# DMX8x8A-v1.net
KiCad netlist of a schematic drawn in Altium Designer
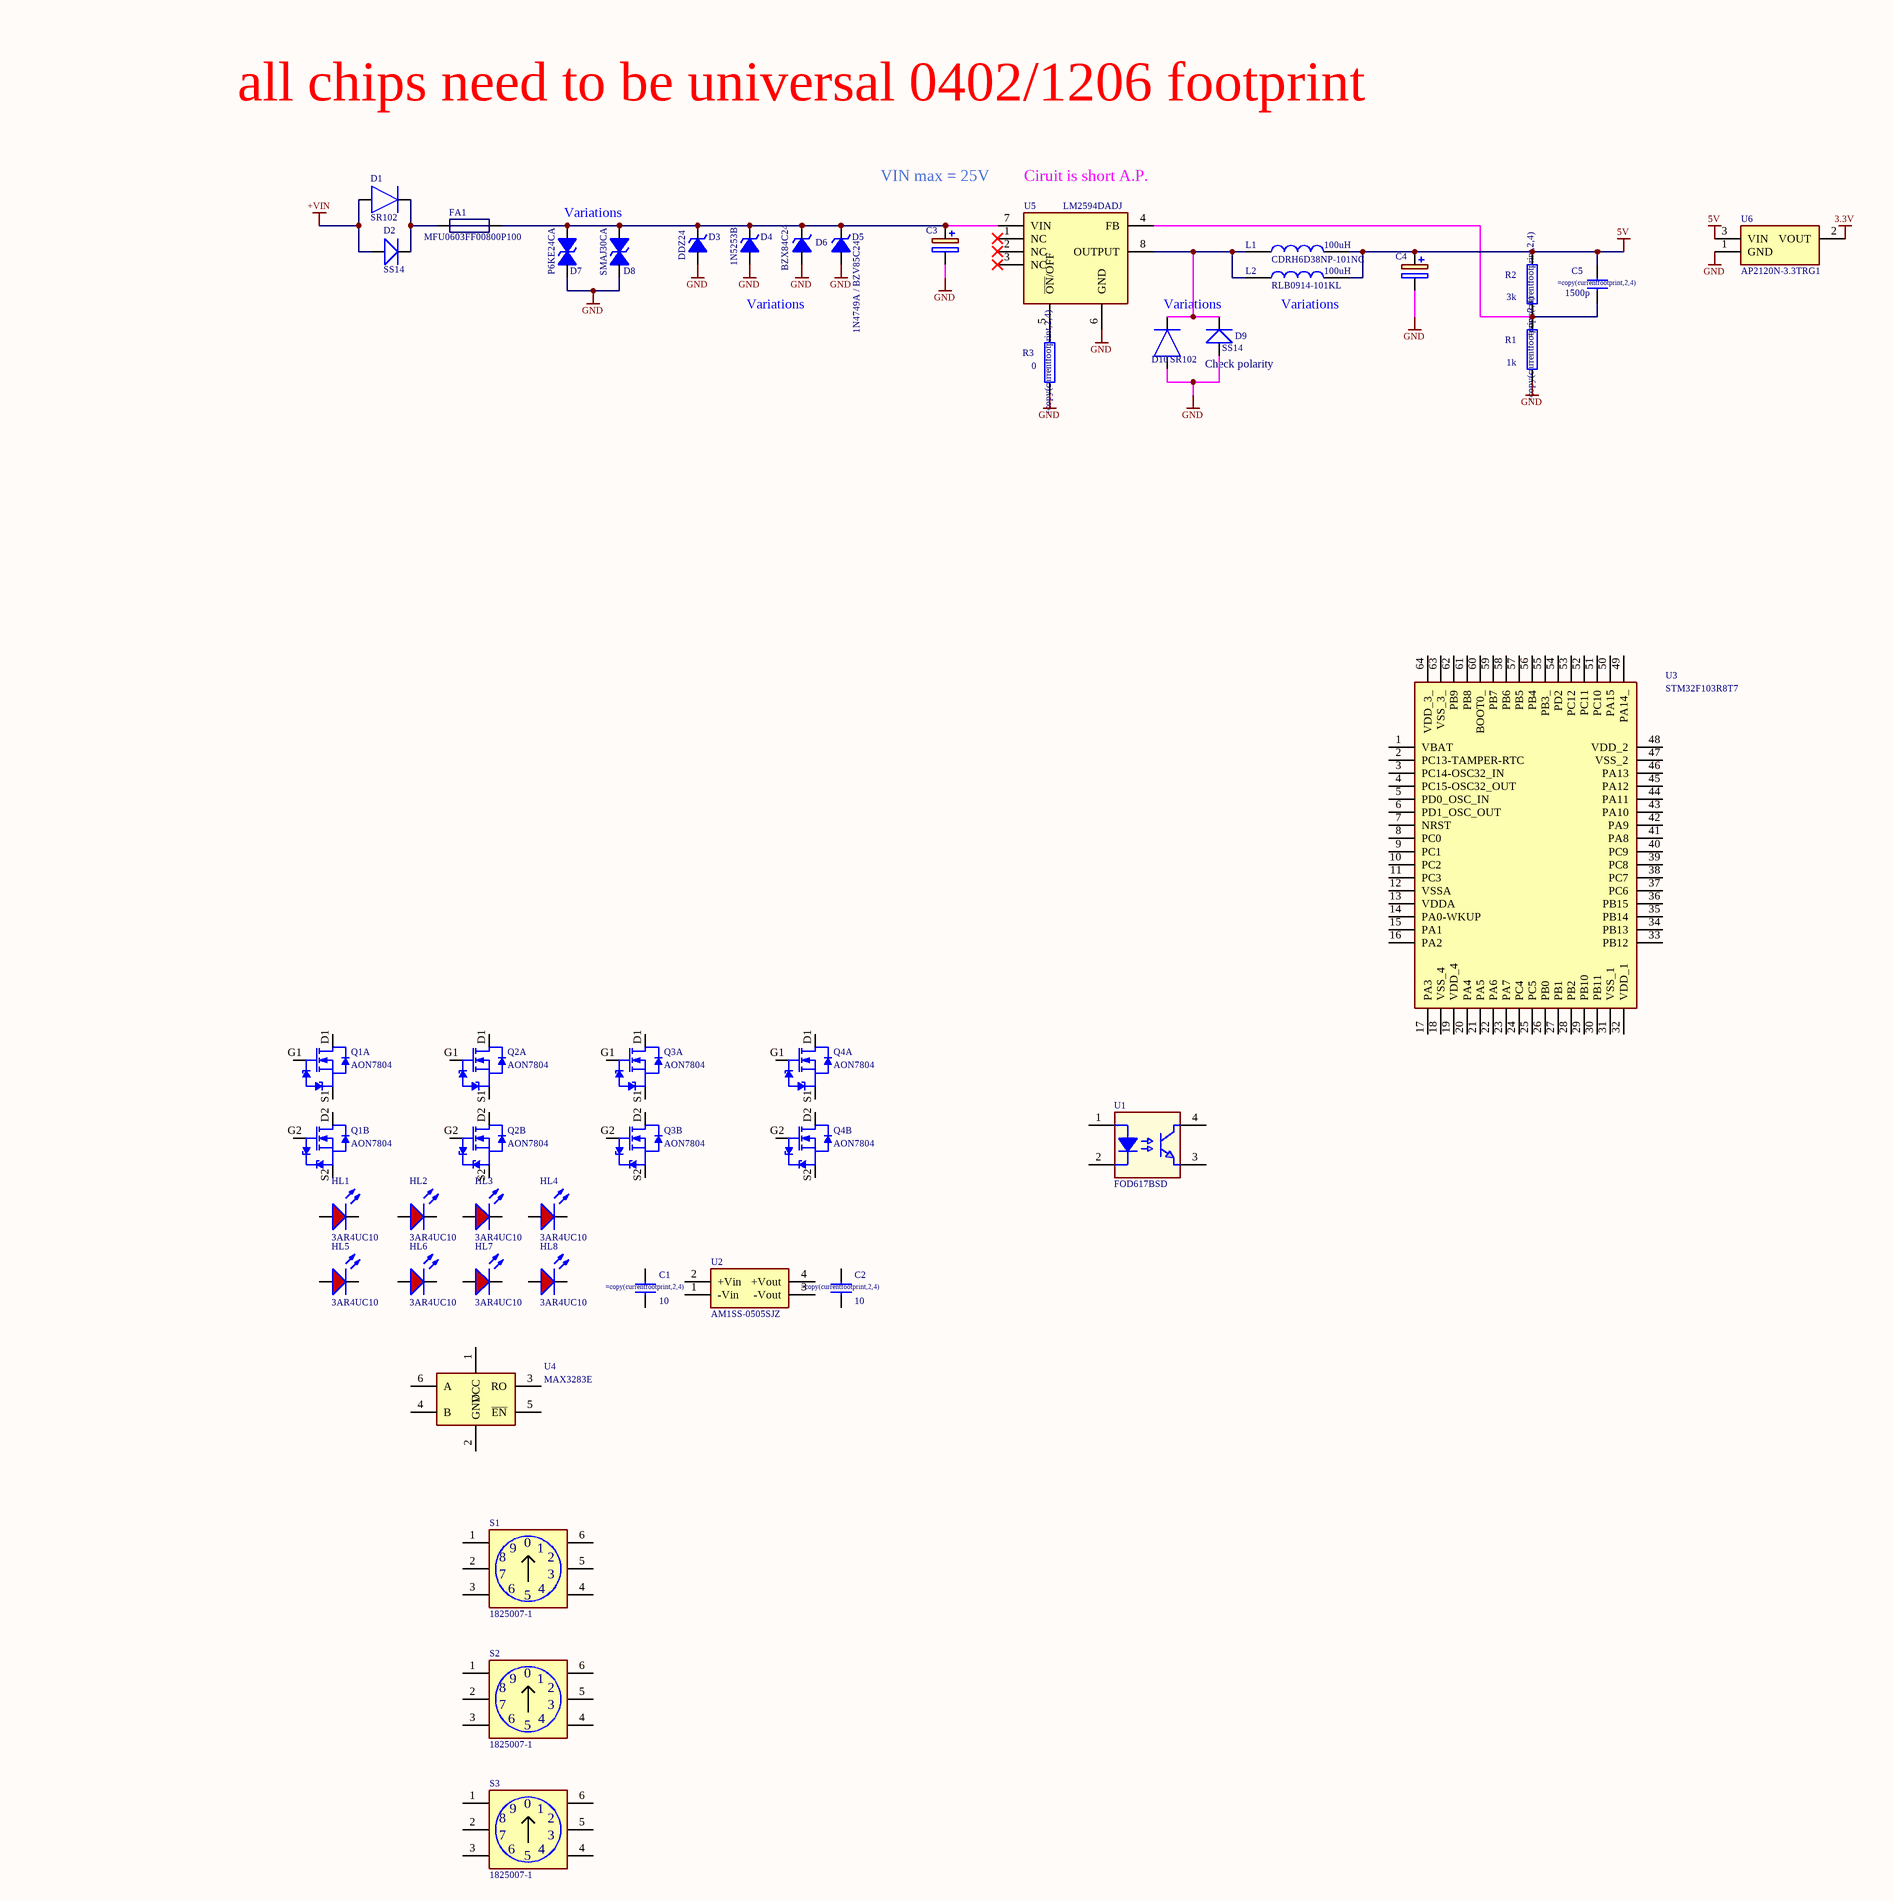
[diagram p0: DMX8x8A-v1.SchDoc]

(export (version "E")
  (design (tool "Eeschema 10.0.6"))
  (components
    (comp (ref "C1")
      (value "10")
      (footprint "C1206_r")
      (description "Ceramic Chip Capacitor")
      (fields (field (name "Comment") "10 50V 5%"))
      (libsource (lib "Capacitors") (part "Ceramic SMD Cap_R"))
    )
    (comp (ref "C2")
      (value "10")
      (footprint "C1206_r")
      (description "Ceramic Chip Capacitor")
      (fields (field (name "Comment") "10 50V 5%"))
      (libsource (lib "Capacitors") (part "Ceramic SMD Cap_R"))
    )
    (comp (ref "C3")
      (value "35ZL470MEFC10X20")
      (footprint "CAPPRD500W60D1025H1750")
      (description "Radial Lead Aluminum Electrolytic Capacitors")
      (libsource (lib "DMX512") (part "35ZL470MEFC10X20"))
    )
    (comp (ref "C4")
      (value "35ZL470MEFC10X20")
      (footprint "CAPPRD500W60D1025H1750")
      (description "Radial Lead Aluminum Electrolytic Capacitors")
      (libsource (lib "DMX512") (part "35ZL470MEFC10X20"))
    )
    (comp (ref "C5")
      (value "1500p")
      (footprint "C0603_r")
      (description "Ceramic Chip Capacitor")
      (fields (field (name "Comment") "1500p 25V 20%"))
      (libsource (lib "Capacitors") (part "Ceramic SMD Cap_R"))
    )
    (comp (ref "D1")
      (value "SR102")
      (footprint "DO-204AL (DO-41)")
      (description "Schottky Barrier Rectifier")
      (libsource (lib "DMX512") (part "SR102"))
    )
    (comp (ref "D2")
      (value "SS14")
      (description "Surface Mount Schottky Barrier Rectifier")
      (libsource (lib "DMX512") (part "SS12"))
    )
    (comp (ref "D3")
      (value "DDZ24")
      (footprint "SOD323F")
      (description "Zener 0.5w SOD323F")
      (fields (field (name "MFR") "Diodes Incorporated"))
      (libsource (lib "Diodes") (part "DDZ"))
    )
    (comp (ref "D4")
      (value "1N5253B")
      (footprint "DO-204AH (DO-35).SLDPRT")
      (description "Zener DO-35")
      (fields (field (name "MFR") "ON Semi"))
      (libsource (lib "DMX512") (part "1N5253B"))
    )
    (comp (ref "D5")
      (value "1N4749A / BZV85C24")
      (footprint "DO-204AL (DO-41)")
      (description "Zener DO-41")
      (libsource (lib "DMX512") (part "Zener DO-41"))
    )
    (comp (ref "D6")
      (value "BZX84C24")
      (footprint "SOT-23-3 (3)")
      (description "Zener regulator, 27V")
      (fields (field (name "MFR") "ON Semi"))
      (libsource (lib "Diodes") (part "BZX84C13LT1G"))
    )
    (comp (ref "D7")
      (value "P6KE24CA")
      (footprint "DIOAD1910W90L670D310 (DO-15)")
      (description "TVS Axial 600W Unipolar 24V")
      (libsource (lib "DMX512") (part "P6KE"))
    )
    (comp (ref "D8")
      (value "SMAJ30CA")
      (footprint "DO-214AC (SMA) biplar")
      (description "TVS Uni 30V")
      (fields (field (name "MFR") "ST"))
      (libsource (lib "TVS") (part "SMAJ30CA"))
    )
    (comp (ref "D9")
      (value "SS14")
      (footprint "DO-214AC (SMA)")
      (description "Surface Mount Schottky Barrier Rectifier")
      (fields (field (name "NOTE") "Check polarity"))
      (libsource (lib "DMX512") (part "SS12"))
    )
    (comp (ref "D10")
      (value "SR102")
      (footprint "DO-204AL (DO-41)")
      (description "Schottky Barrier Rectifier")
      (libsource (lib "DMX512") (part "SR102"))
    )
    (comp (ref "FA1")
      (value "MFU0603FF00800P100")
      (footprint "FUSC1608X55N")
      (description "Thin Film Chip Fuse")
      (libsource (lib "DMX512") (part "Fuse MFU"))
    )
    (comp (ref "HL1")
      (value "3AR4UC10")
      (footprint "LED-2pin 2.54mm")
      (description "LED 3mm Red")
      (libsource (lib "DMX512") (part "3AR4UC10"))
    )
    (comp (ref "HL2")
      (value "3AR4UC10")
      (footprint "LED-2pin 2.54mm")
      (description "LED 3mm Red")
      (libsource (lib "DMX512") (part "3AR4UC10"))
    )
    (comp (ref "HL3")
      (value "3AR4UC10")
      (footprint "LED-2pin 2.54mm")
      (description "LED 3mm Red")
      (libsource (lib "DMX512") (part "3AR4UC10"))
    )
    (comp (ref "HL4")
      (value "3AR4UC10")
      (footprint "LED-2pin 2.54mm")
      (description "LED 3mm Red")
      (libsource (lib "DMX512") (part "3AR4UC10"))
    )
    (comp (ref "HL5")
      (value "3AR4UC10")
      (footprint "LED-2pin 2.54mm")
      (description "LED 3mm Red")
      (libsource (lib "DMX512") (part "3AR4UC10"))
    )
    (comp (ref "HL6")
      (value "3AR4UC10")
      (footprint "LED-2pin 2.54mm")
      (description "LED 3mm Red")
      (libsource (lib "DMX512") (part "3AR4UC10"))
    )
    (comp (ref "HL7")
      (value "3AR4UC10")
      (footprint "LED-2pin 2.54mm")
      (description "LED 3mm Red")
      (libsource (lib "DMX512") (part "3AR4UC10"))
    )
    (comp (ref "HL8")
      (value "3AR4UC10")
      (footprint "LED-2pin 2.54mm")
      (description "LED 3mm Red")
      (libsource (lib "DMX512") (part "3AR4UC10"))
    )
    (comp (ref "L1")
      (value "CDRH6D38NP-101NC")
      (footprint "INDPM6767X400N")
      (description "SMD Power Inductor 100uH 0.65A 265mOhms")
      (fields (field (name "MFR") "Sumida") (field (name "ALTIUM_VALUE") "100uH"))
      (libsource (lib "DMX512") (part "CDRH6D38NP"))
    )
    (comp (ref "L2")
      (value "RLB0914-101KL")
      (footprint "SamacSys:RLB0914")
      (description "Radial Fixed Through Hole Inductor 100uH Bourns 100 uH +/-10%")
      (fields (field (name "ALTIUM_VALUE") "100uH"))
      (libsource (lib "DMX512") (part "RLB0914-101KL"))
    )
    (comp (ref "Q1")
      (value "AON7804")
      (footprint "AON7804")
      (description "30V Dual N-Channel MOSFET")
      (libsource (lib "DMX512") (part "AON7804"))
    )
    (comp (ref "Q2")
      (value "AON7804")
      (footprint "AON7804")
      (description "30V Dual N-Channel MOSFET")
      (libsource (lib "DMX512") (part "AON7804"))
    )
    (comp (ref "Q3")
      (value "AON7804")
      (footprint "AON7804")
      (description "30V Dual N-Channel MOSFET")
      (libsource (lib "DMX512") (part "AON7804"))
    )
    (comp (ref "Q4")
      (value "AON7804")
      (footprint "AON7804")
      (description "30V Dual N-Channel MOSFET")
      (libsource (lib "DMX512") (part "AON7804"))
    )
    (comp (ref "R1")
      (value "1k")
      (footprint "R0402_r")
      (description "Chip Resistor")
      (fields (field (name "Comment") "1k 5%"))
      (libsource (lib "Resistors") (part "SMD Res_R"))
    )
    (comp (ref "R2")
      (value "3k")
      (footprint "R0402_r")
      (description "Chip Resistor")
      (fields (field (name "Comment") "3k 5%"))
      (libsource (lib "Resistors") (part "SMD Res_R"))
    )
    (comp (ref "R3")
      (value "0")
      (footprint "R0402_r")
      (description "Chip Resistor")
      (fields (field (name "Comment") "0 5%"))
      (libsource (lib "Resistors") (part "SMD Res_R"))
    )
    (comp (ref "S1")
      (value "1825007-1")
      (footprint "1825007-1")
      (libsource (lib "DMX512") (part "1825007-1"))
    )
    (comp (ref "S2")
      (value "1825007-1")
      (footprint "1825007-1")
      (libsource (lib "DMX512") (part "1825007-1"))
    )
    (comp (ref "S3")
      (value "1825007-1")
      (footprint "1825007-1")
      (libsource (lib "DMX512") (part "1825007-1"))
    )
    (comp (ref "U1")
      (value "FOD617BSD")
      (footprint "FOD617BSD")
      (description "4-Pin High Operating Temperature\r\nPhototransistor Optocouplers")
      (fields
        (field (name "MANUFACTURER_PART_NUMBER") "FOD814")
        (field (name "MOUSER PART NUMBER") "512-FOD814")
      )
      (libsource (lib "DMX512") (part "FOD617BSD"))
    )
    (comp (ref "U2")
      (value "AM1SS-0505SJZ")
      (footprint "AM1S")
      (description "Isolated DC-DC Converter 1 Watt")
      (fields (field (name "MANUFACTURER_PART_NUMBER") "AM1SS-1205S-NZ"))
      (libsource (lib "DMX512") (part "AM1SS-0505SJZ"))
    )
    (comp (ref "U3")
      (value "STM32F103R8T7")
      (footprint "LQFP64 (QFP50P1200X1200X160-64N)")
      (fields
        (field (name "MOUSER PART NUMBER") "511-STM32F103R8T7")
        (field (name "RS PART NUMBER") "7239025P")
      )
      (libsource (lib "DMX512") (part "STM32F103R8T7"))
    )
    (comp (ref "U4")
      (value "MAX3283E")
      (footprint "SOT23-6 (SOT95P280X145-6N)")
      (description "15kV ESD-Protected 52Mbps, 3V to 5.5V,\r\nSOT23 RS-485/RS-422 True Fail-Safe Receiver")
      (fields
        (field (name "MANUFACTURER_PART_NUMBER") "MAX3283EAUT+T")
        (field (name "MOUSER PART NUMBER") "700-MAX3283EAUTT")
      )
      (libsource (lib "DMX512") (part "MAX3283E"))
    )
    (comp (ref "U5")
      (value "LM2594DADJ")
      (footprint "SOIC-8")
      (description "0.5 A, Step-Down Switching Regulator")
      (fields (field (name "MFR") "ON Semiconductor"))
      (libsource (lib "DMX512") (part "LM2594DADJ"))
    )
    (comp (ref "U6")
      (value "AP2120N-3.3TRG1")
      (footprint "DMX512:SOT-23-3 (3)")
      (description "High Speed, Extremely Low Noise LDO Regulator")
      (fields
        (field (name "MOUSER PART NUMBER") "621-AP2120N-3.3TRG1")
        (field (name "RS PART NUMBER") "8287334P")
      )
      (libsource (lib "DMX512") (part "AP2120N-3.3TRG1"))
    )
  )
  (nets
    (net (code "1") (name "+VIN") (class "Default")
      (node (ref "D1") (pin "2") (pinfunction "A_2") (pintype "passive"))
      (node (ref "D2") (pin "1") (pinfunction "1_1") (pintype "passive"))
    )
    (net (code "2") (name "3.3V") (class "Default")
      (node (ref "U6") (pin "2") (pinfunction "VOUT_2") (pintype "passive"))
    )
    (net (code "3") (name "5V") (class "Default")
      (node (ref "C4") (pin "1") (pinfunction "+_1") (pintype "passive"))
      (node (ref "C5") (pin "2") (pinfunction "2_2") (pintype "passive"))
      (node (ref "L1") (pin "2") (pinfunction "2_2") (pintype "passive"))
      (node (ref "L2") (pin "2") (pinfunction "2_2") (pintype "passive"))
      (node (ref "R2") (pin "2") (pinfunction "BOT_2") (pintype "passive"))
      (node (ref "U6") (pin "3") (pinfunction "VIN_3") (pintype "passive"))
    )
    (net (code "4") (name "GND") (class "Default")
      (node (ref "C3") (pin "2") (pinfunction "-_2") (pintype "passive"))
      (node (ref "C4") (pin "2") (pinfunction "-_2") (pintype "passive"))
      (node (ref "D10") (pin "2") (pinfunction "A_2") (pintype "passive"))
      (node (ref "D3") (pin "2") (pinfunction "A_2") (pintype "passive"))
      (node (ref "D4") (pin "2") (pinfunction "2_2") (pintype "passive"))
      (node (ref "D5") (pin "2") (pinfunction "2_2") (pintype "passive"))
      (node (ref "D6") (pin "1") (pinfunction "1_1") (pintype "passive"))
      (node (ref "D7") (pin "1") (pinfunction "1_1") (pintype "passive"))
      (node (ref "D8") (pin "1") (pinfunction "1_1") (pintype "passive"))
      (node (ref "D9") (pin "1") (pinfunction "1_1") (pintype "passive"))
      (node (ref "R1") (pin "1") (pinfunction "TOP_1") (pintype "passive"))
      (node (ref "R3") (pin "1") (pinfunction "TOP_1") (pintype "passive"))
      (node (ref "U5") (pin "6") (pinfunction "GND_6") (pintype "power_in"))
      (node (ref "U6") (pin "1") (pinfunction "GND_1") (pintype "passive"))
    )
    (net (code "5") (name "Net-(C3-+)") (class "Default")
      (node (ref "C3") (pin "1") (pinfunction "+_1") (pintype "passive"))
      (node (ref "D3") (pin "1") (pinfunction "C_1") (pintype "passive"))
      (node (ref "D4") (pin "1") (pinfunction "1_1") (pintype "passive"))
      (node (ref "D5") (pin "1") (pinfunction "1_1") (pintype "passive"))
      (node (ref "D6") (pin "3") (pinfunction "3_3") (pintype "passive"))
      (node (ref "D7") (pin "2") (pinfunction "2_2") (pintype "passive"))
      (node (ref "D8") (pin "2") (pinfunction "2_2") (pintype "passive"))
      (node (ref "FA1") (pin "2") (pinfunction "2_2") (pintype "passive"))
      (node (ref "U5") (pin "7") (pinfunction "VIN_7") (pintype "passive"))
    )
    (net (code "6") (name "Net-(D1-K)") (class "Default")
      (node (ref "D1") (pin "1") (pinfunction "K_1") (pintype "passive"))
      (node (ref "D2") (pin "2") (pinfunction "2_2") (pintype "passive"))
      (node (ref "FA1") (pin "1") (pinfunction "1_1") (pintype "passive"))
    )
    (net (code "7") (name "Net-(D10-K)") (class "Default")
      (node (ref "D10") (pin "1") (pinfunction "K_1") (pintype "passive"))
      (node (ref "D9") (pin "2") (pinfunction "2_2") (pintype "passive"))
      (node (ref "L1") (pin "1") (pinfunction "1_1") (pintype "passive"))
      (node (ref "L2") (pin "1") (pinfunction "1_1") (pintype "passive"))
      (node (ref "U5") (pin "8") (pinfunction "OUTPUT_8") (pintype "passive"))
    )
    (net (code "8") (name "Net-(R1-BOT)") (class "Default")
      (node (ref "C5") (pin "1") (pinfunction "1_1") (pintype "passive"))
      (node (ref "R1") (pin "2") (pinfunction "BOT_2") (pintype "passive"))
      (node (ref "R2") (pin "1") (pinfunction "TOP_1") (pintype "passive"))
      (node (ref "U5") (pin "4") (pinfunction "FB_4") (pintype "passive"))
    )
    (net (code "9") (name "Net-(R3-BOT)") (class "Default")
      (node (ref "R3") (pin "2") (pinfunction "BOT_2") (pintype "passive"))
      (node (ref "U5") (pin "5") (pinfunction "~{ON}/OFF_5") (pintype "passive"))
    )
    (net (code "10") (name "unconnected-(C1-Pad1)") (class "Default")
      (node (ref "C1") (pin "1") (pinfunction "1_1") (pintype "passive"))
    )
    (net (code "11") (name "unconnected-(C1-Pad2)") (class "Default")
      (node (ref "C1") (pin "2") (pinfunction "2_2") (pintype "passive"))
    )
    (net (code "12") (name "unconnected-(C2-Pad1)") (class "Default")
      (node (ref "C2") (pin "1") (pinfunction "1_1") (pintype "passive"))
    )
    (net (code "13") (name "unconnected-(C2-Pad2)") (class "Default")
      (node (ref "C2") (pin "2") (pinfunction "2_2") (pintype "passive"))
    )
    (net (code "14") (name "unconnected-(HL1-Pad1)") (class "Default")
      (node (ref "HL1") (pin "1") (pinfunction "1_1") (pintype "passive"))
    )
    (net (code "15") (name "unconnected-(HL1-Pad2)") (class "Default")
      (node (ref "HL1") (pin "2") (pinfunction "2_2") (pintype "passive"))
    )
    (net (code "16") (name "unconnected-(HL2-Pad1)") (class "Default")
      (node (ref "HL2") (pin "1") (pinfunction "1_1") (pintype "passive"))
    )
    (net (code "17") (name "unconnected-(HL2-Pad2)") (class "Default")
      (node (ref "HL2") (pin "2") (pinfunction "2_2") (pintype "passive"))
    )
    (net (code "18") (name "unconnected-(HL3-Pad1)") (class "Default")
      (node (ref "HL3") (pin "1") (pinfunction "1_1") (pintype "passive"))
    )
    (net (code "19") (name "unconnected-(HL3-Pad2)") (class "Default")
      (node (ref "HL3") (pin "2") (pinfunction "2_2") (pintype "passive"))
    )
    (net (code "20") (name "unconnected-(HL4-Pad1)") (class "Default")
      (node (ref "HL4") (pin "1") (pinfunction "1_1") (pintype "passive"))
    )
    (net (code "21") (name "unconnected-(HL4-Pad2)") (class "Default")
      (node (ref "HL4") (pin "2") (pinfunction "2_2") (pintype "passive"))
    )
    (net (code "22") (name "unconnected-(HL5-Pad1)") (class "Default")
      (node (ref "HL5") (pin "1") (pinfunction "1_1") (pintype "passive"))
    )
    (net (code "23") (name "unconnected-(HL5-Pad2)") (class "Default")
      (node (ref "HL5") (pin "2") (pinfunction "2_2") (pintype "passive"))
    )
    (net (code "24") (name "unconnected-(HL6-Pad1)") (class "Default")
      (node (ref "HL6") (pin "1") (pinfunction "1_1") (pintype "passive"))
    )
    (net (code "25") (name "unconnected-(HL6-Pad2)") (class "Default")
      (node (ref "HL6") (pin "2") (pinfunction "2_2") (pintype "passive"))
    )
    (net (code "26") (name "unconnected-(HL7-Pad1)") (class "Default")
      (node (ref "HL7") (pin "1") (pinfunction "1_1") (pintype "passive"))
    )
    (net (code "27") (name "unconnected-(HL7-Pad2)") (class "Default")
      (node (ref "HL7") (pin "2") (pinfunction "2_2") (pintype "passive"))
    )
    (net (code "28") (name "unconnected-(HL8-Pad1)") (class "Default")
      (node (ref "HL8") (pin "1") (pinfunction "1_1") (pintype "passive"))
    )
    (net (code "29") (name "unconnected-(HL8-Pad2)") (class "Default")
      (node (ref "HL8") (pin "2") (pinfunction "2_2") (pintype "passive"))
    )
    (net (code "30") (name "unconnected-(Q1-PadD1)") (class "Default")
      (node (ref "Q1") (pin "D1") (pinfunction "D1_D1") (pintype "passive"))
    )
    (net (code "31") (name "unconnected-(Q1-PadD2)") (class "Default")
      (node (ref "Q1") (pin "D2") (pinfunction "D2_D2") (pintype "passive"))
    )
    (net (code "32") (name "unconnected-(Q1-PadG1)") (class "Default")
      (node (ref "Q1") (pin "G1") (pinfunction "G1_G1") (pintype "passive"))
    )
    (net (code "33") (name "unconnected-(Q1-PadS1)") (class "Default")
      (node (ref "Q1") (pin "S1") (pinfunction "S1_S1") (pintype "passive"))
    )
    (net (code "34") (name "unconnected-(Q1B-G1-PadG2)") (class "Default")
      (node (ref "Q1") (pin "G2") (pinfunction "G1_G2") (pintype "passive"))
    )
    (net (code "35") (name "unconnected-(Q1B-S1-PadS2)") (class "Default")
      (node (ref "Q1") (pin "S2") (pinfunction "S1_S2") (pintype "passive"))
    )
    (net (code "36") (name "unconnected-(Q2-PadD1)") (class "Default")
      (node (ref "Q2") (pin "D1") (pinfunction "D1_D1") (pintype "passive"))
    )
    (net (code "37") (name "unconnected-(Q2-PadD2)") (class "Default")
      (node (ref "Q2") (pin "D2") (pinfunction "D2_D2") (pintype "passive"))
    )
    (net (code "38") (name "unconnected-(Q2-PadG1)") (class "Default")
      (node (ref "Q2") (pin "G1") (pinfunction "G1_G1") (pintype "passive"))
    )
    (net (code "39") (name "unconnected-(Q2-PadS1)") (class "Default")
      (node (ref "Q2") (pin "S1") (pinfunction "S1_S1") (pintype "passive"))
    )
    (net (code "40") (name "unconnected-(Q2B-G1-PadG2)") (class "Default")
      (node (ref "Q2") (pin "G2") (pinfunction "G1_G2") (pintype "passive"))
    )
    (net (code "41") (name "unconnected-(Q2B-S1-PadS2)") (class "Default")
      (node (ref "Q2") (pin "S2") (pinfunction "S1_S2") (pintype "passive"))
    )
    (net (code "42") (name "unconnected-(Q3-PadD1)") (class "Default")
      (node (ref "Q3") (pin "D1") (pinfunction "D1_D1") (pintype "passive"))
    )
    (net (code "43") (name "unconnected-(Q3-PadD2)") (class "Default")
      (node (ref "Q3") (pin "D2") (pinfunction "D2_D2") (pintype "passive"))
    )
    (net (code "44") (name "unconnected-(Q3-PadG1)") (class "Default")
      (node (ref "Q3") (pin "G1") (pinfunction "G1_G1") (pintype "passive"))
    )
    (net (code "45") (name "unconnected-(Q3-PadS1)") (class "Default")
      (node (ref "Q3") (pin "S1") (pinfunction "S1_S1") (pintype "passive"))
    )
    (net (code "46") (name "unconnected-(Q3B-G1-PadG2)") (class "Default")
      (node (ref "Q3") (pin "G2") (pinfunction "G1_G2") (pintype "passive"))
    )
    (net (code "47") (name "unconnected-(Q3B-S1-PadS2)") (class "Default")
      (node (ref "Q3") (pin "S2") (pinfunction "S1_S2") (pintype "passive"))
    )
    (net (code "48") (name "unconnected-(Q4-PadD1)") (class "Default")
      (node (ref "Q4") (pin "D1") (pinfunction "D1_D1") (pintype "passive"))
    )
    (net (code "49") (name "unconnected-(Q4-PadD2)") (class "Default")
      (node (ref "Q4") (pin "D2") (pinfunction "D2_D2") (pintype "passive"))
    )
    (net (code "50") (name "unconnected-(Q4-PadG1)") (class "Default")
      (node (ref "Q4") (pin "G1") (pinfunction "G1_G1") (pintype "passive"))
    )
    (net (code "51") (name "unconnected-(Q4-PadS1)") (class "Default")
      (node (ref "Q4") (pin "S1") (pinfunction "S1_S1") (pintype "passive"))
    )
    (net (code "52") (name "unconnected-(Q4B-G1-PadG2)") (class "Default")
      (node (ref "Q4") (pin "G2") (pinfunction "G1_G2") (pintype "passive"))
    )
    (net (code "53") (name "unconnected-(Q4B-S1-PadS2)") (class "Default")
      (node (ref "Q4") (pin "S2") (pinfunction "S1_S2") (pintype "passive"))
    )
    (net (code "54") (name "unconnected-(S1-Pad1)") (class "Default")
      (node (ref "S1") (pin "1") (pinfunction "1_1") (pintype "passive"))
    )
    (net (code "55") (name "unconnected-(S1-Pad2)") (class "Default")
      (node (ref "S1") (pin "2") (pinfunction "2_2") (pintype "passive"))
    )
    (net (code "56") (name "unconnected-(S1-Pad3)") (class "Default")
      (node (ref "S1") (pin "3") (pinfunction "3_3") (pintype "passive"))
    )
    (net (code "57") (name "unconnected-(S1-Pad4)") (class "Default")
      (node (ref "S1") (pin "4") (pinfunction "4_4") (pintype "passive"))
    )
    (net (code "58") (name "unconnected-(S1-Pad5)") (class "Default")
      (node (ref "S1") (pin "5") (pinfunction "5_5") (pintype "passive"))
    )
    (net (code "59") (name "unconnected-(S1-Pad6)") (class "Default")
      (node (ref "S1") (pin "6") (pinfunction "6_6") (pintype "passive"))
    )
    (net (code "60") (name "unconnected-(S2-Pad1)") (class "Default")
      (node (ref "S2") (pin "1") (pinfunction "1_1") (pintype "passive"))
    )
    (net (code "61") (name "unconnected-(S2-Pad2)") (class "Default")
      (node (ref "S2") (pin "2") (pinfunction "2_2") (pintype "passive"))
    )
    (net (code "62") (name "unconnected-(S2-Pad3)") (class "Default")
      (node (ref "S2") (pin "3") (pinfunction "3_3") (pintype "passive"))
    )
    (net (code "63") (name "unconnected-(S2-Pad4)") (class "Default")
      (node (ref "S2") (pin "4") (pinfunction "4_4") (pintype "passive"))
    )
    (net (code "64") (name "unconnected-(S2-Pad5)") (class "Default")
      (node (ref "S2") (pin "5") (pinfunction "5_5") (pintype "passive"))
    )
    (net (code "65") (name "unconnected-(S2-Pad6)") (class "Default")
      (node (ref "S2") (pin "6") (pinfunction "6_6") (pintype "passive"))
    )
    (net (code "66") (name "unconnected-(S3-Pad1)") (class "Default")
      (node (ref "S3") (pin "1") (pinfunction "1_1") (pintype "passive"))
    )
    (net (code "67") (name "unconnected-(S3-Pad2)") (class "Default")
      (node (ref "S3") (pin "2") (pinfunction "2_2") (pintype "passive"))
    )
    (net (code "68") (name "unconnected-(S3-Pad3)") (class "Default")
      (node (ref "S3") (pin "3") (pinfunction "3_3") (pintype "passive"))
    )
    (net (code "69") (name "unconnected-(S3-Pad4)") (class "Default")
      (node (ref "S3") (pin "4") (pinfunction "4_4") (pintype "passive"))
    )
    (net (code "70") (name "unconnected-(S3-Pad5)") (class "Default")
      (node (ref "S3") (pin "5") (pinfunction "5_5") (pintype "passive"))
    )
    (net (code "71") (name "unconnected-(S3-Pad6)") (class "Default")
      (node (ref "S3") (pin "6") (pinfunction "6_6") (pintype "passive"))
    )
    (net (code "72") (name "unconnected-(U1-A-Pad1)") (class "Default")
      (node (ref "U1") (pin "1") (pinfunction "A_1") (pintype "passive"))
    )
    (net (code "73") (name "unconnected-(U1-C-Pad2)") (class "Default")
      (node (ref "U1") (pin "2") (pinfunction "C_2") (pintype "passive"))
    )
    (net (code "74") (name "unconnected-(U1-C-Pad4)") (class "Default")
      (node (ref "U1") (pin "4") (pinfunction "C_4") (pintype "passive"))
    )
    (net (code "75") (name "unconnected-(U1-E-Pad3)") (class "Default")
      (node (ref "U1") (pin "3") (pinfunction "E_3") (pintype "passive"))
    )
    (net (code "76") (name "unconnected-(U2-+Vin-Pad2)") (class "Default")
      (node (ref "U2") (pin "2") (pinfunction "+Vin_2") (pintype "passive"))
    )
    (net (code "77") (name "unconnected-(U2-+Vout-Pad4)") (class "Default")
      (node (ref "U2") (pin "4") (pinfunction "+Vout_4") (pintype "passive"))
    )
    (net (code "78") (name "unconnected-(U2--Vin-Pad1)") (class "Default")
      (node (ref "U2") (pin "1") (pinfunction "-Vin_1") (pintype "passive"))
    )
    (net (code "79") (name "unconnected-(U2--Vout-Pad3)") (class "Default")
      (node (ref "U2") (pin "3") (pinfunction "-Vout_3") (pintype "passive"))
    )
    (net (code "80") (name "unconnected-(U3-BOOT0_-Pad60)") (class "Default")
      (node (ref "U3") (pin "60") (pinfunction "BOOT0__60") (pintype "passive"))
    )
    (net (code "81") (name "unconnected-(U3-NRST-Pad7)") (class "Default")
      (node (ref "U3") (pin "7") (pinfunction "NRST_7") (pintype "passive"))
    )
    (net (code "82") (name "unconnected-(U3-PA0-WKUP-Pad14)") (class "Default")
      (node (ref "U3") (pin "14") (pinfunction "PA0-WKUP_14") (pintype "passive"))
    )
    (net (code "83") (name "unconnected-(U3-PA1-Pad15)") (class "Default")
      (node (ref "U3") (pin "15") (pinfunction "PA1_15") (pintype "passive"))
    )
    (net (code "84") (name "unconnected-(U3-PA2-Pad16)") (class "Default")
      (node (ref "U3") (pin "16") (pinfunction "PA2_16") (pintype "passive"))
    )
    (net (code "85") (name "unconnected-(U3-PA3-Pad17)") (class "Default")
      (node (ref "U3") (pin "17") (pinfunction "PA3_17") (pintype "passive"))
    )
    (net (code "86") (name "unconnected-(U3-PA4-Pad20)") (class "Default")
      (node (ref "U3") (pin "20") (pinfunction "PA4_20") (pintype "passive"))
    )
    (net (code "87") (name "unconnected-(U3-PA5-Pad21)") (class "Default")
      (node (ref "U3") (pin "21") (pinfunction "PA5_21") (pintype "passive"))
    )
    (net (code "88") (name "unconnected-(U3-PA6-Pad22)") (class "Default")
      (node (ref "U3") (pin "22") (pinfunction "PA6_22") (pintype "passive"))
    )
    (net (code "89") (name "unconnected-(U3-PA7-Pad23)") (class "Default")
      (node (ref "U3") (pin "23") (pinfunction "PA7_23") (pintype "passive"))
    )
    (net (code "90") (name "unconnected-(U3-PA8-Pad41)") (class "Default")
      (node (ref "U3") (pin "41") (pinfunction "PA8_41") (pintype "passive"))
    )
    (net (code "91") (name "unconnected-(U3-PA9-Pad42)") (class "Default")
      (node (ref "U3") (pin "42") (pinfunction "PA9_42") (pintype "passive"))
    )
    (net (code "92") (name "unconnected-(U3-PA10-Pad43)") (class "Default")
      (node (ref "U3") (pin "43") (pinfunction "PA10_43") (pintype "passive"))
    )
    (net (code "93") (name "unconnected-(U3-PA11-Pad44)") (class "Default")
      (node (ref "U3") (pin "44") (pinfunction "PA11_44") (pintype "passive"))
    )
    (net (code "94") (name "unconnected-(U3-PA12-Pad45)") (class "Default")
      (node (ref "U3") (pin "45") (pinfunction "PA12_45") (pintype "passive"))
    )
    (net (code "95") (name "unconnected-(U3-PA13-Pad46)") (class "Default")
      (node (ref "U3") (pin "46") (pinfunction "PA13_46") (pintype "passive"))
    )
    (net (code "96") (name "unconnected-(U3-PA14_-Pad49)") (class "Default")
      (node (ref "U3") (pin "49") (pinfunction "PA14__49") (pintype "passive"))
    )
    (net (code "97") (name "unconnected-(U3-PA15-Pad50)") (class "Default")
      (node (ref "U3") (pin "50") (pinfunction "PA15_50") (pintype "passive"))
    )
    (net (code "98") (name "unconnected-(U3-PB0-Pad26)") (class "Default")
      (node (ref "U3") (pin "26") (pinfunction "PB0_26") (pintype "passive"))
    )
    (net (code "99") (name "unconnected-(U3-PB1-Pad27)") (class "Default")
      (node (ref "U3") (pin "27") (pinfunction "PB1_27") (pintype "passive"))
    )
    (net (code "100") (name "unconnected-(U3-PB2-Pad28)") (class "Default")
      (node (ref "U3") (pin "28") (pinfunction "PB2_28") (pintype "passive"))
    )
    (net (code "101") (name "unconnected-(U3-PB3_-Pad55)") (class "Default")
      (node (ref "U3") (pin "55") (pinfunction "PB3__55") (pintype "passive"))
    )
    (net (code "102") (name "unconnected-(U3-PB4-Pad56)") (class "Default")
      (node (ref "U3") (pin "56") (pinfunction "PB4_56") (pintype "passive"))
    )
    (net (code "103") (name "unconnected-(U3-PB5-Pad57)") (class "Default")
      (node (ref "U3") (pin "57") (pinfunction "PB5_57") (pintype "passive"))
    )
    (net (code "104") (name "unconnected-(U3-PB6-Pad58)") (class "Default")
      (node (ref "U3") (pin "58") (pinfunction "PB6_58") (pintype "passive"))
    )
    (net (code "105") (name "unconnected-(U3-PB7-Pad59)") (class "Default")
      (node (ref "U3") (pin "59") (pinfunction "PB7_59") (pintype "passive"))
    )
    (net (code "106") (name "unconnected-(U3-PB8-Pad61)") (class "Default")
      (node (ref "U3") (pin "61") (pinfunction "PB8_61") (pintype "passive"))
    )
    (net (code "107") (name "unconnected-(U3-PB9-Pad62)") (class "Default")
      (node (ref "U3") (pin "62") (pinfunction "PB9_62") (pintype "passive"))
    )
    (net (code "108") (name "unconnected-(U3-PB10-Pad29)") (class "Default")
      (node (ref "U3") (pin "29") (pinfunction "PB10_29") (pintype "passive"))
    )
    (net (code "109") (name "unconnected-(U3-PB11-Pad30)") (class "Default")
      (node (ref "U3") (pin "30") (pinfunction "PB11_30") (pintype "passive"))
    )
    (net (code "110") (name "unconnected-(U3-PB12-Pad33)") (class "Default")
      (node (ref "U3") (pin "33") (pinfunction "PB12_33") (pintype "passive"))
    )
    (net (code "111") (name "unconnected-(U3-PB13-Pad34)") (class "Default")
      (node (ref "U3") (pin "34") (pinfunction "PB13_34") (pintype "passive"))
    )
    (net (code "112") (name "unconnected-(U3-PB14-Pad35)") (class "Default")
      (node (ref "U3") (pin "35") (pinfunction "PB14_35") (pintype "passive"))
    )
    (net (code "113") (name "unconnected-(U3-PB15-Pad36)") (class "Default")
      (node (ref "U3") (pin "36") (pinfunction "PB15_36") (pintype "passive"))
    )
    (net (code "114") (name "unconnected-(U3-PC0-Pad8)") (class "Default")
      (node (ref "U3") (pin "8") (pinfunction "PC0_8") (pintype "passive"))
    )
    (net (code "115") (name "unconnected-(U3-PC1-Pad9)") (class "Default")
      (node (ref "U3") (pin "9") (pinfunction "PC1_9") (pintype "passive"))
    )
    (net (code "116") (name "unconnected-(U3-PC2-Pad10)") (class "Default")
      (node (ref "U3") (pin "10") (pinfunction "PC2_10") (pintype "passive"))
    )
    (net (code "117") (name "unconnected-(U3-PC3-Pad11)") (class "Default")
      (node (ref "U3") (pin "11") (pinfunction "PC3_11") (pintype "passive"))
    )
    (net (code "118") (name "unconnected-(U3-PC4-Pad24)") (class "Default")
      (node (ref "U3") (pin "24") (pinfunction "PC4_24") (pintype "passive"))
    )
    (net (code "119") (name "unconnected-(U3-PC5-Pad25)") (class "Default")
      (node (ref "U3") (pin "25") (pinfunction "PC5_25") (pintype "passive"))
    )
    (net (code "120") (name "unconnected-(U3-PC6-Pad37)") (class "Default")
      (node (ref "U3") (pin "37") (pinfunction "PC6_37") (pintype "passive"))
    )
    (net (code "121") (name "unconnected-(U3-PC7-Pad38)") (class "Default")
      (node (ref "U3") (pin "38") (pinfunction "PC7_38") (pintype "passive"))
    )
    (net (code "122") (name "unconnected-(U3-PC8-Pad39)") (class "Default")
      (node (ref "U3") (pin "39") (pinfunction "PC8_39") (pintype "passive"))
    )
    (net (code "123") (name "unconnected-(U3-PC9-Pad40)") (class "Default")
      (node (ref "U3") (pin "40") (pinfunction "PC9_40") (pintype "passive"))
    )
    (net (code "124") (name "unconnected-(U3-PC10-Pad51)") (class "Default")
      (node (ref "U3") (pin "51") (pinfunction "PC10_51") (pintype "passive"))
    )
    (net (code "125") (name "unconnected-(U3-PC11-Pad52)") (class "Default")
      (node (ref "U3") (pin "52") (pinfunction "PC11_52") (pintype "passive"))
    )
    (net (code "126") (name "unconnected-(U3-PC12-Pad53)") (class "Default")
      (node (ref "U3") (pin "53") (pinfunction "PC12_53") (pintype "passive"))
    )
    (net (code "127") (name "unconnected-(U3-PC13-TAMPER-RTC-Pad2)") (class "Default")
      (node (ref "U3") (pin "2") (pinfunction "PC13-TAMPER-RTC_2") (pintype "passive"))
    )
    (net (code "128") (name "unconnected-(U3-PC14-OSC32_IN-Pad3)") (class "Default")
      (node (ref "U3") (pin "3") (pinfunction "PC14-OSC32_IN_3") (pintype "passive"))
    )
    (net (code "129") (name "unconnected-(U3-PC15-OSC32_OUT-Pad4)") (class "Default")
      (node (ref "U3") (pin "4") (pinfunction "PC15-OSC32_OUT_4") (pintype "passive"))
    )
    (net (code "130") (name "unconnected-(U3-PD0_OSC_IN-Pad5)") (class "Default")
      (node (ref "U3") (pin "5") (pinfunction "PD0_OSC_IN_5") (pintype "passive"))
    )
    (net (code "131") (name "unconnected-(U3-PD1_OSC_OUT-Pad6)") (class "Default")
      (node (ref "U3") (pin "6") (pinfunction "PD1_OSC_OUT_6") (pintype "passive"))
    )
    (net (code "132") (name "unconnected-(U3-PD2-Pad54)") (class "Default")
      (node (ref "U3") (pin "54") (pinfunction "PD2_54") (pintype "passive"))
    )
    (net (code "133") (name "unconnected-(U3-VBAT-Pad1)") (class "Default")
      (node (ref "U3") (pin "1") (pinfunction "VBAT_1") (pintype "passive"))
    )
    (net (code "134") (name "unconnected-(U3-VDDA-Pad13)") (class "Default")
      (node (ref "U3") (pin "13") (pinfunction "VDDA_13") (pintype "passive"))
    )
    (net (code "135") (name "unconnected-(U3-VDD_1-Pad32)") (class "Default")
      (node (ref "U3") (pin "32") (pinfunction "VDD_1_32") (pintype "power_in"))
    )
    (net (code "136") (name "unconnected-(U3-VDD_2-Pad48)") (class "Default")
      (node (ref "U3") (pin "48") (pinfunction "VDD_2_48") (pintype "power_in"))
    )
    (net (code "137") (name "unconnected-(U3-VDD_3_-Pad64)") (class "Default")
      (node (ref "U3") (pin "64") (pinfunction "VDD_3__64") (pintype "power_in"))
    )
    (net (code "138") (name "unconnected-(U3-VDD_4-Pad19)") (class "Default")
      (node (ref "U3") (pin "19") (pinfunction "VDD_4_19") (pintype "power_in"))
    )
    (net (code "139") (name "unconnected-(U3-VSSA-Pad12)") (class "Default")
      (node (ref "U3") (pin "12") (pinfunction "VSSA_12") (pintype "passive"))
    )
    (net (code "140") (name "unconnected-(U3-VSS_1-Pad31)") (class "Default")
      (node (ref "U3") (pin "31") (pinfunction "VSS_1_31") (pintype "power_in"))
    )
    (net (code "141") (name "unconnected-(U3-VSS_2-Pad47)") (class "Default")
      (node (ref "U3") (pin "47") (pinfunction "VSS_2_47") (pintype "power_in"))
    )
    (net (code "142") (name "unconnected-(U3-VSS_3_-Pad63)") (class "Default")
      (node (ref "U3") (pin "63") (pinfunction "VSS_3__63") (pintype "power_in"))
    )
    (net (code "143") (name "unconnected-(U3-VSS_4-Pad18)") (class "Default")
      (node (ref "U3") (pin "18") (pinfunction "VSS_4_18") (pintype "power_in"))
    )
    (net (code "144") (name "unconnected-(U4-A-Pad6)") (class "Default")
      (node (ref "U4") (pin "6") (pinfunction "A_6") (pintype "passive"))
    )
    (net (code "145") (name "unconnected-(U4-B-Pad4)") (class "Default")
      (node (ref "U4") (pin "4") (pinfunction "B_4") (pintype "passive"))
    )
    (net (code "146") (name "unconnected-(U4-GND-Pad2)") (class "Default")
      (node (ref "U4") (pin "2") (pinfunction "GND_2") (pintype "power_in"))
    )
    (net (code "147") (name "unconnected-(U4-RO-Pad3)") (class "Default")
      (node (ref "U4") (pin "3") (pinfunction "RO_3") (pintype "passive"))
    )
    (net (code "148") (name "unconnected-(U4-VCC-Pad1)") (class "Default")
      (node (ref "U4") (pin "1") (pinfunction "VCC_1") (pintype "power_in"))
    )
    (net (code "149") (name "unconnected-(U4-~{EN}-Pad5)") (class "Default")
      (node (ref "U4") (pin "5") (pinfunction "~{EN}_5") (pintype "passive"))
    )
    (net (code "150") (name "unconnected-(U5-NC-Pad1)") (class "Default")
      (node (ref "U5") (pin "1") (pinfunction "NC_1") (pintype "passive+no_connect"))
    )
    (net (code "151") (name "unconnected-(U5-NC-Pad2)") (class "Default")
      (node (ref "U5") (pin "2") (pinfunction "NC_2") (pintype "passive+no_connect"))
    )
    (net (code "152") (name "unconnected-(U5-NC-Pad3)") (class "Default")
      (node (ref "U5") (pin "3") (pinfunction "NC_3") (pintype "passive+no_connect"))
    )
  )
)
